# vga_breakout.net
KiCad netlist of a schematic drawn in EAGLE
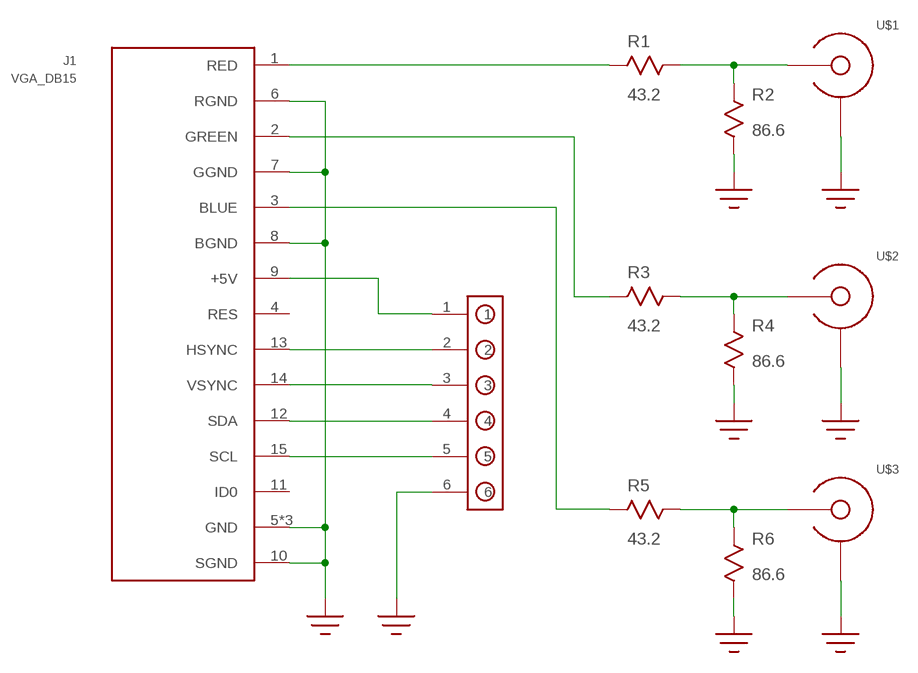
[diagram p0: schematic, sheet 1]

(export (version "E")
  (design (tool "Eeschema 10.0.6"))
  (components
    (comp (ref "J1")
      (value "VGA_DB15")
      (footprint "eagle-import:VGA_PCB_MALE")
      (libsource (lib "eagle-import") (part "VGA_DB15"))
    )
    (comp (ref "R1")
      (value "43.2")
      (footprint "eagle-import:R0805")
      (libsource (lib "eagle-import") (part "R0805"))
    )
    (comp (ref "R2")
      (value "86.6")
      (footprint "eagle-import:R0805")
      (libsource (lib "eagle-import") (part "R0805"))
    )
    (comp (ref "R3")
      (value "43.2")
      (footprint "eagle-import:R0805")
      (libsource (lib "eagle-import") (part "R0805"))
    )
    (comp (ref "R4")
      (value "86.6")
      (footprint "eagle-import:R0805")
      (libsource (lib "eagle-import") (part "R0805"))
    )
    (comp (ref "R5")
      (value "43.2")
      (footprint "eagle-import:R0805")
      (libsource (lib "eagle-import") (part "R0805"))
    )
    (comp (ref "R6")
      (value "86.6")
      (footprint "eagle-import:R0805")
      (libsource (lib "eagle-import") (part "R0805"))
    )
    (comp (ref "U$1")
      (value "EDGE_LAUNCH_JACK")
      (footprint "eagle-import:EDGE_LAUNCH_RF_CON")
      (libsource (lib "eagle-import") (part "EDGE_LAUNCH_JACK"))
    )
    (comp (ref "U$2")
      (value "EDGE_LAUNCH_JACK")
      (footprint "eagle-import:EDGE_LAUNCH_RF_CON")
      (libsource (lib "eagle-import") (part "EDGE_LAUNCH_JACK"))
    )
    (comp (ref "U$3")
      (value "EDGE_LAUNCH_JACK")
      (footprint "eagle-import:EDGE_LAUNCH_RF_CON")
      (libsource (lib "eagle-import") (part "EDGE_LAUNCH_JACK"))
    )
    (comp (ref "U$9")
      (value "HEADER_6P")
      (footprint "eagle-import:HEADER_6P")
      (libsource (lib "eagle-import") (part "HEADER_6P"))
    )
  )
  (nets
    (net (code "1") (name "GND") (class "Default")
      (node (ref "J1") (pin "10") (pinfunction "SGND_10") (pintype "bidirectional"))
      (node (ref "J1") (pin "5") (pinfunction "GND_5") (pintype "bidirectional"))
      (node (ref "J1") (pin "6") (pinfunction "RGND_6") (pintype "bidirectional"))
      (node (ref "J1") (pin "7") (pinfunction "GGND_7") (pintype "bidirectional"))
      (node (ref "J1") (pin "8") (pinfunction "BGND_8") (pintype "bidirectional"))
      (node (ref "J1") (pin "TAB@1") (pinfunction "GND_TAB@1") (pintype "bidirectional"))
      (node (ref "J1") (pin "TAB@2") (pinfunction "GND_TAB@2") (pintype "bidirectional"))
      (node (ref "R2") (pin "P$2") (pinfunction "P$4_P$2") (pintype "bidirectional"))
      (node (ref "R4") (pin "P$1") (pinfunction "P$3_P$1") (pintype "bidirectional"))
      (node (ref "R6") (pin "P$2") (pinfunction "P$4_P$2") (pintype "bidirectional"))
      (node (ref "U$1") (pin "GND@1") (pinfunction "SHIELD_GND@1") (pintype "bidirectional"))
      (node (ref "U$1") (pin "GND@10") (pinfunction "SHIELD_GND@10") (pintype "bidirectional"))
      (node (ref "U$1") (pin "GND@11") (pinfunction "SHIELD_GND@11") (pintype "bidirectional"))
      (node (ref "U$1") (pin "GND@12") (pinfunction "SHIELD_GND@12") (pintype "bidirectional"))
      (node (ref "U$1") (pin "GND@2") (pinfunction "SHIELD_GND@2") (pintype "bidirectional"))
      (node (ref "U$1") (pin "GND@3") (pinfunction "SHIELD_GND@3") (pintype "bidirectional"))
      (node (ref "U$1") (pin "GND@4") (pinfunction "SHIELD_GND@4") (pintype "bidirectional"))
      (node (ref "U$1") (pin "GND@5") (pinfunction "SHIELD_GND@5") (pintype "bidirectional"))
      (node (ref "U$1") (pin "GND@6") (pinfunction "SHIELD_GND@6") (pintype "bidirectional"))
      (node (ref "U$1") (pin "GND@7") (pinfunction "SHIELD_GND@7") (pintype "bidirectional"))
      (node (ref "U$1") (pin "GND@8") (pinfunction "SHIELD_GND@8") (pintype "bidirectional"))
      (node (ref "U$1") (pin "GND@9") (pinfunction "SHIELD_GND@9") (pintype "bidirectional"))
      (node (ref "U$1") (pin "SHIELD@1") (pinfunction "SHIELD_SHIELD@1") (pintype "bidirectional"))
      (node (ref "U$1") (pin "SHIELD@2") (pinfunction "SHIELD_SHIELD@2") (pintype "bidirectional"))
      (node (ref "U$2") (pin "GND@1") (pinfunction "SHIELD_GND@1") (pintype "bidirectional"))
      (node (ref "U$2") (pin "GND@10") (pinfunction "SHIELD_GND@10") (pintype "bidirectional"))
      (node (ref "U$2") (pin "GND@11") (pinfunction "SHIELD_GND@11") (pintype "bidirectional"))
      (node (ref "U$2") (pin "GND@12") (pinfunction "SHIELD_GND@12") (pintype "bidirectional"))
      (node (ref "U$2") (pin "GND@2") (pinfunction "SHIELD_GND@2") (pintype "bidirectional"))
      (node (ref "U$2") (pin "GND@3") (pinfunction "SHIELD_GND@3") (pintype "bidirectional"))
      (node (ref "U$2") (pin "GND@4") (pinfunction "SHIELD_GND@4") (pintype "bidirectional"))
      (node (ref "U$2") (pin "GND@5") (pinfunction "SHIELD_GND@5") (pintype "bidirectional"))
      (node (ref "U$2") (pin "GND@6") (pinfunction "SHIELD_GND@6") (pintype "bidirectional"))
      (node (ref "U$2") (pin "GND@7") (pinfunction "SHIELD_GND@7") (pintype "bidirectional"))
      (node (ref "U$2") (pin "GND@8") (pinfunction "SHIELD_GND@8") (pintype "bidirectional"))
      (node (ref "U$2") (pin "GND@9") (pinfunction "SHIELD_GND@9") (pintype "bidirectional"))
      (node (ref "U$2") (pin "SHIELD@1") (pinfunction "SHIELD_SHIELD@1") (pintype "bidirectional"))
      (node (ref "U$2") (pin "SHIELD@2") (pinfunction "SHIELD_SHIELD@2") (pintype "bidirectional"))
      (node (ref "U$3") (pin "GND@1") (pinfunction "SHIELD_GND@1") (pintype "bidirectional"))
      (node (ref "U$3") (pin "GND@10") (pinfunction "SHIELD_GND@10") (pintype "bidirectional"))
      (node (ref "U$3") (pin "GND@11") (pinfunction "SHIELD_GND@11") (pintype "bidirectional"))
      (node (ref "U$3") (pin "GND@12") (pinfunction "SHIELD_GND@12") (pintype "bidirectional"))
      (node (ref "U$3") (pin "GND@2") (pinfunction "SHIELD_GND@2") (pintype "bidirectional"))
      (node (ref "U$3") (pin "GND@3") (pinfunction "SHIELD_GND@3") (pintype "bidirectional"))
      (node (ref "U$3") (pin "GND@4") (pinfunction "SHIELD_GND@4") (pintype "bidirectional"))
      (node (ref "U$3") (pin "GND@5") (pinfunction "SHIELD_GND@5") (pintype "bidirectional"))
      (node (ref "U$3") (pin "GND@6") (pinfunction "SHIELD_GND@6") (pintype "bidirectional"))
      (node (ref "U$3") (pin "GND@7") (pinfunction "SHIELD_GND@7") (pintype "bidirectional"))
      (node (ref "U$3") (pin "GND@8") (pinfunction "SHIELD_GND@8") (pintype "bidirectional"))
      (node (ref "U$3") (pin "GND@9") (pinfunction "SHIELD_GND@9") (pintype "bidirectional"))
      (node (ref "U$3") (pin "SHIELD@1") (pinfunction "SHIELD_SHIELD@1") (pintype "bidirectional"))
      (node (ref "U$3") (pin "SHIELD@2") (pinfunction "SHIELD_SHIELD@2") (pintype "bidirectional"))
      (node (ref "U$9") (pin "6") (pinfunction "6_6") (pintype "bidirectional"))
    )
    (net (code "2") (name "Net-(J1-+5V)") (class "Default")
      (node (ref "J1") (pin "9") (pinfunction "+5V_9") (pintype "bidirectional"))
      (node (ref "U$9") (pin "1") (pinfunction "1_1") (pintype "bidirectional"))
    )
    (net (code "3") (name "Net-(J1-BLUE)") (class "Default")
      (node (ref "J1") (pin "3") (pinfunction "BLUE_3") (pintype "bidirectional"))
      (node (ref "R5") (pin "P$2") (pinfunction "P$4_P$2") (pintype "bidirectional"))
    )
    (net (code "4") (name "Net-(J1-GREEN)") (class "Default")
      (node (ref "J1") (pin "2") (pinfunction "GREEN_2") (pintype "bidirectional"))
      (node (ref "R3") (pin "P$2") (pinfunction "P$4_P$2") (pintype "bidirectional"))
    )
    (net (code "5") (name "Net-(J1-HSYNC)") (class "Default")
      (node (ref "J1") (pin "13") (pinfunction "HSYNC_13") (pintype "bidirectional"))
      (node (ref "U$9") (pin "2") (pinfunction "2_2") (pintype "bidirectional"))
    )
    (net (code "6") (name "Net-(J1-RED)") (class "Default")
      (node (ref "J1") (pin "1") (pinfunction "RED_1") (pintype "bidirectional"))
      (node (ref "R1") (pin "P$1") (pinfunction "P$3_P$1") (pintype "bidirectional"))
    )
    (net (code "7") (name "Net-(J1-SCL)") (class "Default")
      (node (ref "J1") (pin "15") (pinfunction "SCL_15") (pintype "bidirectional"))
      (node (ref "U$9") (pin "5") (pinfunction "5_5") (pintype "bidirectional"))
    )
    (net (code "8") (name "Net-(J1-SDA)") (class "Default")
      (node (ref "J1") (pin "12") (pinfunction "SDA_12") (pintype "bidirectional"))
      (node (ref "U$9") (pin "4") (pinfunction "4_4") (pintype "bidirectional"))
    )
    (net (code "9") (name "Net-(J1-VSYNC)") (class "Default")
      (node (ref "J1") (pin "14") (pinfunction "VSYNC_14") (pintype "bidirectional"))
      (node (ref "U$9") (pin "3") (pinfunction "3_3") (pintype "bidirectional"))
    )
    (net (code "10") (name "Net-(R1-P$4)") (class "Default")
      (node (ref "R1") (pin "P$2") (pinfunction "P$4_P$2") (pintype "bidirectional"))
      (node (ref "R2") (pin "P$1") (pinfunction "P$3_P$1") (pintype "bidirectional"))
      (node (ref "U$1") (pin "CENTER") (pinfunction "CENTER_CENTER") (pintype "bidirectional"))
    )
    (net (code "11") (name "Net-(R3-P$3)") (class "Default")
      (node (ref "R3") (pin "P$1") (pinfunction "P$3_P$1") (pintype "bidirectional"))
      (node (ref "R4") (pin "P$2") (pinfunction "P$4_P$2") (pintype "bidirectional"))
      (node (ref "U$2") (pin "CENTER") (pinfunction "CENTER_CENTER") (pintype "bidirectional"))
    )
    (net (code "12") (name "Net-(R5-P$3)") (class "Default")
      (node (ref "R5") (pin "P$1") (pinfunction "P$3_P$1") (pintype "bidirectional"))
      (node (ref "R6") (pin "P$1") (pinfunction "P$3_P$1") (pintype "bidirectional"))
      (node (ref "U$3") (pin "CENTER") (pinfunction "CENTER_CENTER") (pintype "bidirectional"))
    )
    (net (code "13") (name "unconnected-(J1-ID0-Pad11)") (class "Default")
      (node (ref "J1") (pin "11") (pinfunction "ID0_11") (pintype "bidirectional"))
    )
    (net (code "14") (name "unconnected-(J1-RES-Pad4)") (class "Default")
      (node (ref "J1") (pin "4") (pinfunction "RES_4") (pintype "bidirectional"))
    )
  )
)
